# 48V-5V_Buck.net
KiCad netlist of a schematic drawn in Altium Designer
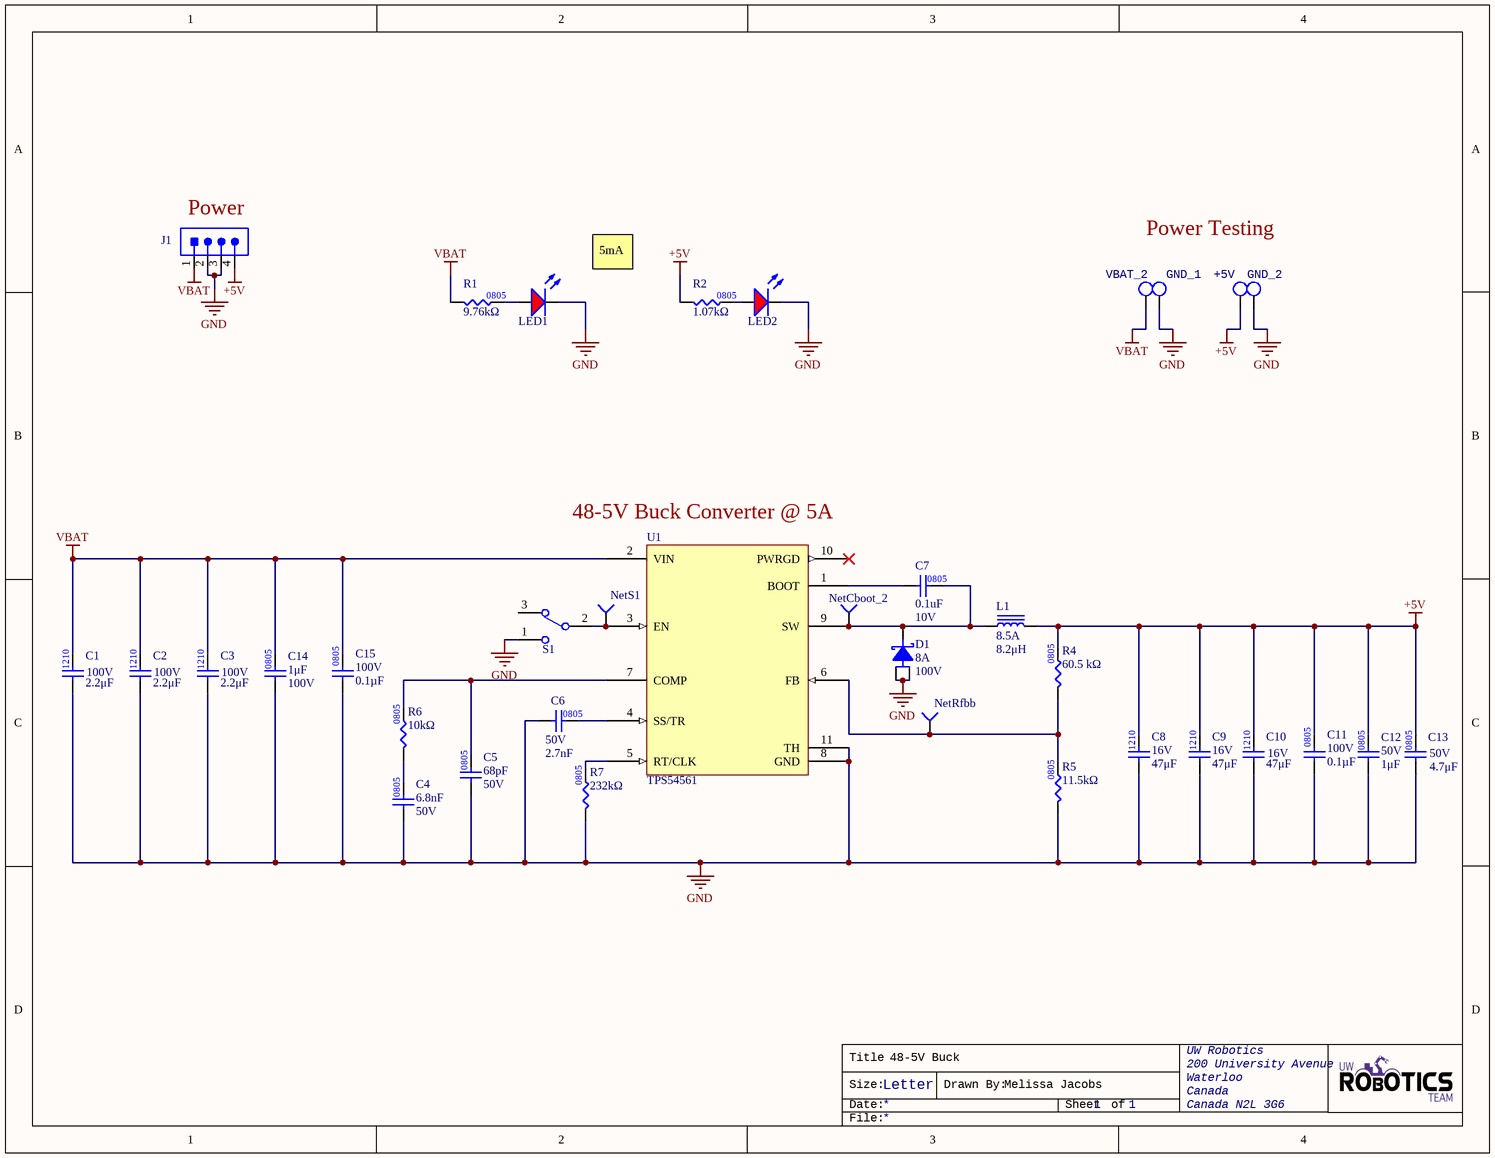
[diagram p0: 48V-5V Buck.SchDoc]

(export (version "E")
  (design (tool "Eeschema 10.0.6"))
  (components
    (comp (ref "+5V")
      (value "TESTPOINT_LOOP")
      (footprint "TESTPOINT_LOOP")
      (description "TESTPOINT THRUHOLE")
      (libsource (lib "UWRT_Schematic_Library_2020") (part "TESTPOINT_LOOP"))
    )
    (comp (ref "C1")
      (value "2.2μF")
      (footprint "CAPC3225X270N")
      (description "CAP CER 2.2UF 100V X7R 1210")
      (fields (field (name "VOLTAGE RATING") "100V") (field (name "Comment") "CAP_2.2uF_100V_1210_1"))
      (libsource (lib "UWRT_Schematic_Library_2020") (part "CAP_2.2uF_100V_1210_1"))
    )
    (comp (ref "C2")
      (value "2.2μF")
      (footprint "CAPC3225X270N")
      (description "CAP CER 2.2UF 100V X7R 1210")
      (fields (field (name "VOLTAGE RATING") "100V") (field (name "Comment") "CAP_2.2uF_100V_1210_1"))
      (libsource (lib "UWRT_Schematic_Library_2020") (part "CAP_2.2uF_100V_1210_1"))
    )
    (comp (ref "C3")
      (value "2.2μF")
      (footprint "CAPC3225X270N")
      (description "CAP CER 2.2UF 100V X7R 1210")
      (fields (field (name "VOLTAGE RATING") "100V") (field (name "Comment") "CAP_2.2uF_100V_1210_1"))
      (libsource (lib "UWRT_Schematic_Library_2020") (part "CAP_2.2uF_100V_1210_1"))
    )
    (comp (ref "C4")
      (value "6.8nF")
      (footprint "CAP0805")
      (description "CAP CER 6800PF 50V C0G/NP0 0805")
      (fields (field (name "VOLTAGE RATING") "50V") (field (name "Comment") "CAP_6.8nF_100V_0805"))
      (libsource (lib "UWRT_Schematic_Library_2020") (part "CAP_6.8nF_100V_0805"))
    )
    (comp (ref "C5")
      (value "68pF")
      (footprint "CAP0805")
      (description "CAP CER 68PF 50V C0G/NP0 0805")
      (fields (field (name "VOLTAGE RATING") "50V") (field (name "Comment") "CAP_68pF_50V_0805"))
      (libsource (lib "UWRT_Schematic_Library_2020") (part "CAP_68pF_50V_0805"))
    )
    (comp (ref "C6")
      (value "2.7nF")
      (footprint "CAP0805")
      (description "CAP CER 2700PF 50V C0G 0805")
      (fields (field (name "VOLTAGE RATING") "50V") (field (name "Comment") "CAP_2.7nF_50V_0805"))
      (libsource (lib "UWRT_Schematic_Library_2020") (part "CAP_2.7nF_50V_0805"))
    )
    (comp (ref "C7")
      (value "0.1uF")
      (footprint "CAP0805")
      (description "CAP CER 0.1uF 10V 0805")
      (fields (field (name "VOLTAGE RATING") "10V") (field (name "Comment") "CAP_0.1uF_10V_0805"))
      (libsource (lib "UWRT_Schematic_Library_2020") (part "CAP_0.1uF_10V_0805"))
    )
    (comp (ref "C8")
      (value "47μF")
      (footprint "CAPC3225X270N")
      (description "CAP CER 47uF 16V X5R 1210")
      (fields (field (name "VOLTAGE RATING") "16V") (field (name "Comment") "CAP_47uF_16V_1210"))
      (libsource (lib "UWRT_Schematic_Library_2020") (part "CAP_47uF_16V_1210"))
    )
    (comp (ref "C9")
      (value "47μF")
      (footprint "CAPC3225X270N")
      (description "CAP CER 47uF 16V X5R 1210")
      (fields (field (name "VOLTAGE RATING") "16V") (field (name "Comment") "CAP_47uF_16V_1210"))
      (libsource (lib "UWRT_Schematic_Library_2020") (part "CAP_47uF_16V_1210"))
    )
    (comp (ref "C10")
      (value "47μF")
      (footprint "CAPC3225X270N")
      (description "CAP CER 47uF 16V X5R 1210")
      (fields (field (name "VOLTAGE RATING") "16V") (field (name "Comment") "CAP_47uF_16V_1210"))
      (libsource (lib "UWRT_Schematic_Library_2020") (part "CAP_47uF_16V_1210"))
    )
    (comp (ref "C11")
      (value "0.1µF")
      (footprint "CAP0805")
      (description "CAP CER 0.1UF 100V X7R 0805")
      (fields (field (name "VOLTAGE RATING") "100V") (field (name "Comment") "CAP_0.1uF_100V_0805"))
      (libsource (lib "UWRT_Schematic_Library_2020") (part "CAP_0.1uF_100V_0805"))
    )
    (comp (ref "C12")
      (value "1μF")
      (footprint "CAP0805")
      (description "CAP CER 1UF 50V X7R 0805")
      (fields
        (field (name "LCSC PART #") "C28323")
        (field (name "VOLTAGE RATING") "50V")
        (field (name "Comment") "CAP_1uF_50V_0805")
      )
      (libsource (lib "UWRT_Schematic_Library_2020") (part "CAP_1uF_50V_0805"))
    )
    (comp (ref "C13")
      (value "4.7μF")
      (footprint "CAP0805")
      (description "CAP CER 4.7UF 50V X5R 0805")
      (fields
        (field (name "LCSC PART #") "C1779")
        (field (name "VOLTAGE RATING") "50V")
        (field (name "Comment") "CAP_4.7uF_50V_0805")
      )
      (libsource (lib "UWRT_Schematic_Library_2020") (part "CAP_4.7uF_50V_0805"))
    )
    (comp (ref "C14")
      (value "1μF")
      (footprint "CAP0805")
      (description "CAP CER 1UF 100V X7S 0805")
      (fields (field (name "VOLTAGE RATING") "100V") (field (name "Comment") "CAP_1uF_100V_0805"))
      (libsource (lib "UWRT_Schematic_Library_2020") (part "CAP_1uF_100V_0805"))
    )
    (comp (ref "C15")
      (value "0.1µF")
      (footprint "CAP0805")
      (description "CAP CER 0.1UF 100V X7R 0805")
      (fields (field (name "VOLTAGE RATING") "100V") (field (name "Comment") "CAP_0.1uF_100V_0805"))
      (libsource (lib "UWRT_Schematic_Library_2020") (part "CAP_0.1uF_100V_0805"))
    )
    (comp (ref "D1")
      (value "8A")
      (footprint "TO-277")
      (description "Diode 100 V 8A Surface Mount TO-277")
      (fields (field (name "VR (MAX)") "100V"))
      (libsource (lib "UWRT_Schematic_Library_2020") (part "DIO_SCHOTTKY_100V_8A"))
    )
    (comp (ref "GND_1")
      (value "TESTPOINT_LOOP")
      (footprint "TESTPOINT_LOOP")
      (description "TESTPOINT THRUHOLE")
      (libsource (lib "UWRT_Schematic_Library_2020") (part "TESTPOINT_LOOP"))
    )
    (comp (ref "GND_2")
      (value "TESTPOINT_LOOP")
      (footprint "TESTPOINT_LOOP")
      (description "TESTPOINT THRUHOLE")
      (libsource (lib "UWRT_Schematic_Library_2020") (part "TESTPOINT_LOOP"))
    )
    (comp (ref "J1")
      (value "CON_2POS_SCREW_TERM")
      (footprint "MPT-04-01-01-L-RA-SD")
      (description "CONN HDR 4POS 5MM R/A SLDR")
      (libsource (lib "UWRT_Schematic_Library_2020") (part "CON_4POS_POWERBLADE_MALE"))
    )
    (comp (ref "L1")
      (value "8.2μH")
      (footprint "IND_8.2uH_8.5A")
      (description "FIXED IND 8.2UH 8.5A 28 MOHM SMD")
      (fields (field (name "CURRENT RATING") "8.5A") (field (name "Comment") "IND_8.2uH_8.5A"))
      (libsource (lib "UWRT_Schematic_Library_2020") (part "IND_8.2uH_8.5A"))
    )
    (comp (ref "LED1")
      (value "LED_RED")
      (footprint "LED_0805_RED")
      (description "LED RED DIFFUSED 0805 SMD")
      (libsource (lib "UWRT_Schematic_Library_2020") (part "LED_RED"))
    )
    (comp (ref "LED2")
      (value "LED_RED")
      (footprint "LED_0805_RED")
      (description "LED RED DIFFUSED 0805 SMD")
      (libsource (lib "UWRT_Schematic_Library_2020") (part "LED_RED"))
    )
    (comp (ref "NetCboot_2")
      (value "TESTPOINT_1MM_CIRCLE")
      (footprint "TESTPOINT_CIRCLE_1MM")
      (description "TESTPOINT 1MM CIRCLE")
      (libsource (lib "UWRT_Schematic_Library_2020") (part "TESTPOINT_1MM_CIRCLE"))
    )
    (comp (ref "NetRfbb")
      (value "TESTPOINT_1MM_CIRCLE")
      (footprint "TESTPOINT_CIRCLE_1MM")
      (description "TESTPOINT 1MM CIRCLE")
      (libsource (lib "UWRT_Schematic_Library_2020") (part "TESTPOINT_1MM_CIRCLE"))
    )
    (comp (ref "NetS1")
      (value "TESTPOINT_1MM_CIRCLE")
      (footprint "TESTPOINT_CIRCLE_1MM")
      (description "TESTPOINT 1MM CIRCLE")
      (libsource (lib "UWRT_Schematic_Library_2020") (part "TESTPOINT_1MM_CIRCLE"))
    )
    (comp (ref "R1")
      (value "9.76kΩ")
      (footprint "RES0805")
      (description "RES 9.76K OHM 1% 1/8W 0805")
      (fields (field (name "Comment") "RES_9.76kΩ_0805_1%"))
      (libsource (lib "UWRT_Schematic_Library_2020") (part "RES_9.76kΩ_0805_1%"))
    )
    (comp (ref "R2")
      (value "1.07kΩ")
      (footprint "RES0805")
      (description "RES 1K OHM 1% 1/8W 0805")
      (fields (field (name "Comment") "RES_1kΩ_0805_1%"))
      (libsource (lib "UWRT_Schematic_Library_2020") (part "RES_1kΩ_0805_1%"))
    )
    (comp (ref "R4")
      (value "60.5 kΩ")
      (footprint "RES0805")
      (description "RES 60.5 kOHM 63 mW 0805")
      (fields (field (name "Comment") "RES_60.4kΩ_0805_1%"))
      (libsource (lib "UWRT_Schematic_Library_2020") (part "RES_60.4kΩ_0805_1%"))
    )
    (comp (ref "R5")
      (value "11.5kΩ")
      (footprint "RES0805")
      (description "RES 11.5K OHM 0.1% 1/10W 0805")
      (fields (field (name "Comment") "RES_11.5kΩ_0805_0.1%"))
      (libsource (lib "UWRT_Schematic_Library_2020") (part "RES_11.5kΩ_0805_0.1%"))
    )
    (comp (ref "R6")
      (value "10kΩ")
      (footprint "RES0805")
      (description "RES 10K OHM 5% 1/8W 0805")
      (fields (field (name "LCSC PART #") "C17414") (field (name "Comment") "RES_10kΩ_0805_5%"))
      (libsource (lib "UWRT_Schematic_Library_2020") (part "RES_10kΩ_0805_5%"))
    )
    (comp (ref "R7")
      (value "232kΩ")
      (footprint "RES0805")
      (description "RES 232K OHM 1% 1/8W 0805")
      (fields (field (name "LCSC PART #") "0") (field (name "Comment") "RES_232kΩ_0805_1%"))
      (libsource (lib "UWRT_Schematic_Library_2020") (part "RES_232kΩ_0805_1%"))
    )
    (comp (ref "S1")
      (value "SW_SLIDE_TOGGLE")
      (footprint "UWRT_Footprint_Library_2020:SW_SLIDE_TOGGLE")
      (description "SWITCH SLIDE SPDT 200MA 30V")
      (libsource (lib "UWRT_Schematic_Library_2020") (part "SW_SLIDE_TOGGLE"))
    )
    (comp (ref "U1")
      (value "TPS54561")
      (footprint "BUCK_TPS54561DPRR")
      (description "Buck Switching Regulator IC Positive Adjustable 0.8V 1 Output 5A 10-WDFN Exposed Pad")
      (libsource (lib "UWRT_Schematic_Library_2020") (part "TPS54561"))
    )
    (comp (ref "VBAT_2")
      (value "TESTPOINT_LOOP")
      (footprint "TESTPOINT_LOOP")
      (description "TESTPOINT THRUHOLE")
      (libsource (lib "UWRT_Schematic_Library_2020") (part "TESTPOINT_LOOP"))
    )
  )
  (nets
    (net (code "1") (name "+5V") (class "Default")
      (node (ref "+5V") (pin "1") (pintype "passive"))
      (node (ref "C10") (pin "2") (pinfunction "2_2") (pintype "passive"))
      (node (ref "C11") (pin "2") (pinfunction "2_2") (pintype "passive"))
      (node (ref "C12") (pin "2") (pinfunction "2_2") (pintype "passive"))
      (node (ref "C13") (pin "2") (pinfunction "2_2") (pintype "passive"))
      (node (ref "C8") (pin "2") (pinfunction "2_2") (pintype "passive"))
      (node (ref "C9") (pin "2") (pinfunction "2_2") (pintype "passive"))
      (node (ref "J1") (pin "4") (pinfunction "2_4") (pintype "passive"))
      (node (ref "L1") (pin "2") (pinfunction "2_2") (pintype "passive"))
      (node (ref "R2") (pin "1") (pinfunction "1_1") (pintype "passive"))
      (node (ref "R4") (pin "2") (pinfunction "2_2") (pintype "passive"))
    )
    (net (code "2") (name "GND") (class "Default")
      (node (ref "C1") (pin "1") (pinfunction "1_1") (pintype "passive"))
      (node (ref "C10") (pin "1") (pinfunction "1_1") (pintype "passive"))
      (node (ref "C11") (pin "1") (pinfunction "1_1") (pintype "passive"))
      (node (ref "C12") (pin "1") (pinfunction "1_1") (pintype "passive"))
      (node (ref "C13") (pin "1") (pinfunction "1_1") (pintype "passive"))
      (node (ref "C14") (pin "1") (pinfunction "1_1") (pintype "passive"))
      (node (ref "C15") (pin "1") (pinfunction "1_1") (pintype "passive"))
      (node (ref "C2") (pin "1") (pinfunction "1_1") (pintype "passive"))
      (node (ref "C3") (pin "1") (pinfunction "1_1") (pintype "passive"))
      (node (ref "C4") (pin "1") (pinfunction "1_1") (pintype "passive"))
      (node (ref "C5") (pin "1") (pinfunction "1_1") (pintype "passive"))
      (node (ref "C6") (pin "1") (pinfunction "1_1") (pintype "passive"))
      (node (ref "C8") (pin "1") (pinfunction "1_1") (pintype "passive"))
      (node (ref "C9") (pin "1") (pinfunction "1_1") (pintype "passive"))
      (node (ref "D1") (pin "1") (pinfunction "Anode_1") (pintype "passive"))
      (node (ref "D1") (pin "3") (pintype "passive"))
      (node (ref "GND_1") (pin "1") (pintype "passive"))
      (node (ref "GND_2") (pin "1") (pintype "passive"))
      (node (ref "J1") (pin "2") (pinfunction "2_2") (pintype "passive"))
      (node (ref "J1") (pin "3") (pinfunction "1_3") (pintype "passive"))
      (node (ref "LED1") (pin "2") (pinfunction "K_2") (pintype "passive"))
      (node (ref "LED2") (pin "2") (pinfunction "K_2") (pintype "passive"))
      (node (ref "R5") (pin "1") (pinfunction "1_1") (pintype "passive"))
      (node (ref "R7") (pin "1") (pinfunction "1_1") (pintype "passive"))
      (node (ref "S1") (pin "1") (pinfunction "1_1") (pintype "passive"))
      (node (ref "U1") (pin "11") (pinfunction "TH_11") (pintype "power_in"))
      (node (ref "U1") (pin "8") (pinfunction "GND_8") (pintype "power_in"))
    )
    (net (code "3") (name "Net-(C4-Pad2)") (class "Default")
      (node (ref "C4") (pin "2") (pinfunction "2_2") (pintype "passive"))
      (node (ref "R6") (pin "1") (pinfunction "1_1") (pintype "passive"))
    )
    (net (code "4") (name "Net-(D1-Cathode)") (class "Default")
      (node (ref "C7") (pin "2") (pinfunction "2_2") (pintype "passive"))
      (node (ref "D1") (pin "2") (pinfunction "Cathode_2") (pintype "passive"))
      (node (ref "L1") (pin "1") (pinfunction "1_1") (pintype "passive"))
      (node (ref "NetCboot_2") (pin "1") (pinfunction "=value_1") (pintype "passive"))
      (node (ref "U1") (pin "9") (pinfunction "SW_9") (pintype "power_in"))
    )
    (net (code "5") (name "Net-(LED1-A)") (class "Default")
      (node (ref "LED1") (pin "1") (pinfunction "A_1") (pintype "passive"))
      (node (ref "R1") (pin "2") (pinfunction "2_2") (pintype "passive"))
    )
    (net (code "6") (name "Net-(LED2-A)") (class "Default")
      (node (ref "LED2") (pin "1") (pinfunction "A_1") (pintype "passive"))
      (node (ref "R2") (pin "2") (pinfunction "2_2") (pintype "passive"))
    )
    (net (code "7") (name "Net-(NetRfbb-=value)") (class "Default")
      (node (ref "NetRfbb") (pin "1") (pinfunction "=value_1") (pintype "passive"))
      (node (ref "R4") (pin "1") (pinfunction "1_1") (pintype "passive"))
      (node (ref "R5") (pin "2") (pinfunction "2_2") (pintype "passive"))
      (node (ref "U1") (pin "6") (pinfunction "FB_6") (pintype "input"))
    )
    (net (code "8") (name "Net-(NetS1-=value)") (class "Default")
      (node (ref "NetS1") (pin "1") (pinfunction "=value_1") (pintype "passive"))
      (node (ref "S1") (pin "2") (pinfunction "2_2") (pintype "passive"))
      (node (ref "U1") (pin "3") (pinfunction "EN_3") (pintype "input"))
    )
    (net (code "9") (name "Net-(U1-BOOT)") (class "Default")
      (node (ref "C7") (pin "1") (pinfunction "1_1") (pintype "passive"))
      (node (ref "U1") (pin "1") (pinfunction "BOOT_1") (pintype "power_in"))
    )
    (net (code "10") (name "Net-(U1-COMP)") (class "Default")
      (node (ref "C5") (pin "2") (pinfunction "2_2") (pintype "passive"))
      (node (ref "R6") (pin "2") (pinfunction "2_2") (pintype "passive"))
      (node (ref "U1") (pin "7") (pinfunction "COMP_7") (pintype "power_in"))
    )
    (net (code "11") (name "Net-(U1-RT{slash}CLK)") (class "Default")
      (node (ref "R7") (pin "2") (pinfunction "2_2") (pintype "passive"))
      (node (ref "U1") (pin "5") (pinfunction "RT/CLK_5") (pintype "input"))
    )
    (net (code "12") (name "Net-(U1-SS{slash}TR)") (class "Default")
      (node (ref "C6") (pin "2") (pinfunction "2_2") (pintype "passive"))
      (node (ref "U1") (pin "4") (pinfunction "SS/TR_4") (pintype "input"))
    )
    (net (code "13") (name "VBAT") (class "Default")
      (node (ref "C1") (pin "2") (pinfunction "2_2") (pintype "passive"))
      (node (ref "C14") (pin "2") (pinfunction "2_2") (pintype "passive"))
      (node (ref "C15") (pin "2") (pinfunction "2_2") (pintype "passive"))
      (node (ref "C2") (pin "2") (pinfunction "2_2") (pintype "passive"))
      (node (ref "C3") (pin "2") (pinfunction "2_2") (pintype "passive"))
      (node (ref "J1") (pin "1") (pinfunction "1_1") (pintype "passive"))
      (node (ref "R1") (pin "1") (pinfunction "1_1") (pintype "passive"))
      (node (ref "U1") (pin "2") (pinfunction "VIN_2") (pintype "power_in"))
      (node (ref "VBAT_2") (pin "1") (pintype "passive"))
    )
    (net (code "14") (name "unconnected-(S1-Pad3)") (class "Default")
      (node (ref "S1") (pin "3") (pinfunction "3_3") (pintype "passive"))
    )
    (net (code "15") (name "unconnected-(U1-PWRGD-Pad10)") (class "Default")
      (node (ref "U1") (pin "10") (pinfunction "PWRGD_10") (pintype "output+no_connect"))
    )
  )
)
